# fpga30-serdes-power.net
KiCad netlist of a schematic drawn in Altium Designer
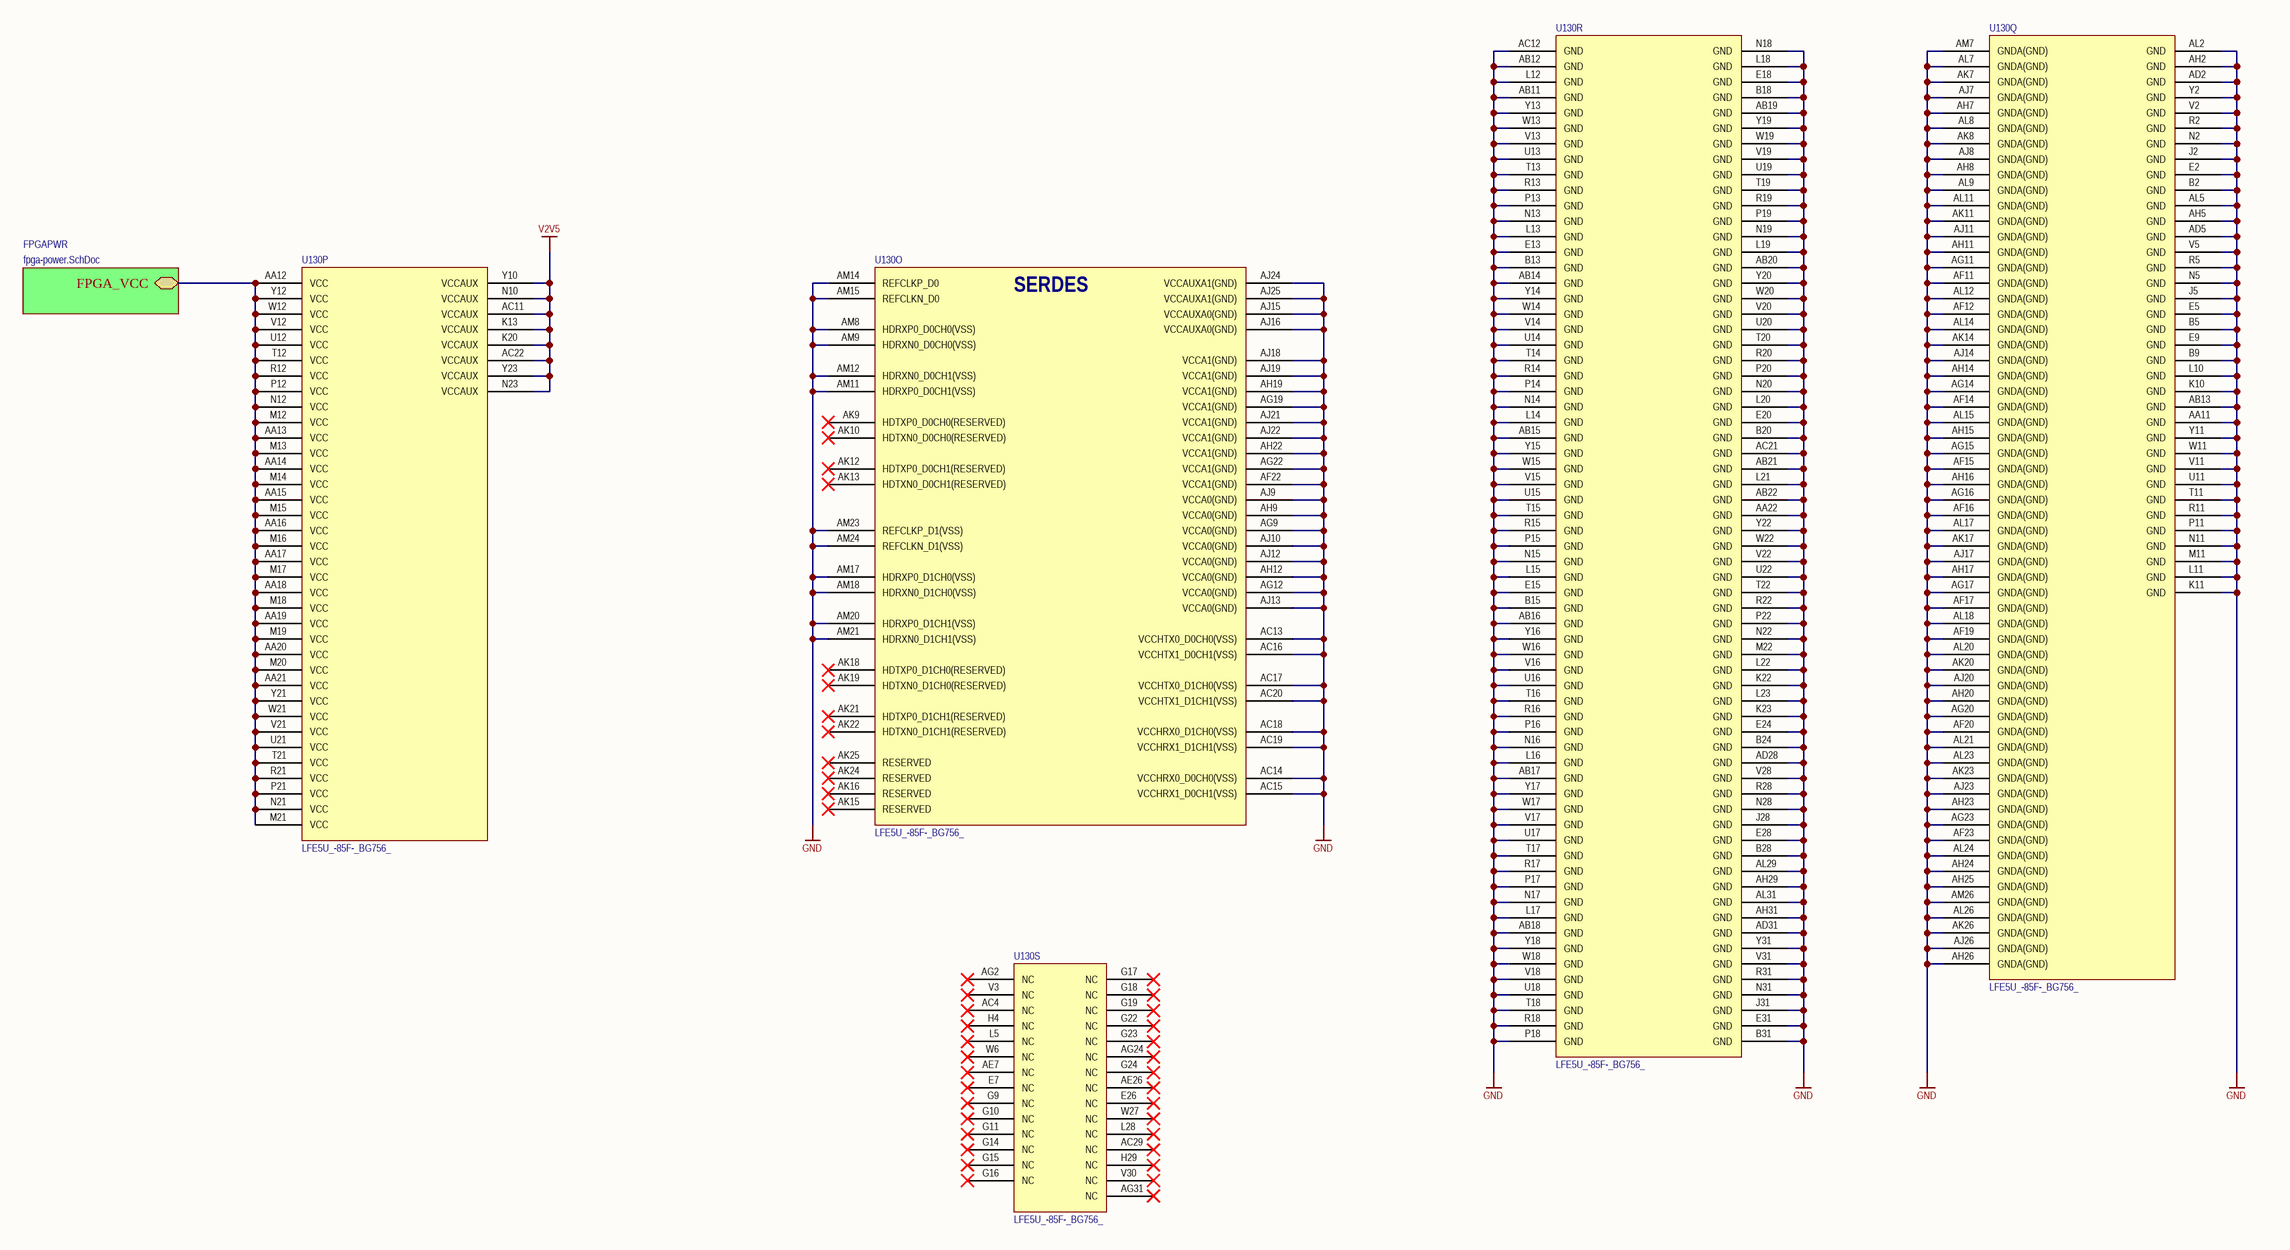
[diagram p0: fpga30-serdes-power.SchDoc]

(export (version "E")
  (design (tool "Eeschema 10.0.6"))
  (components
    (comp (ref "U130")
      (value "LFE5U_-85F-_BG756_")
      (footprint "lattice:caBGA756")
      (description "ECP5 FPGA, 85k LUT, 756-caBGA")
      (fields (field (name "MANUFACTURER") "Lattice Semiconductor"))
      (libsource (lib "lattice") (part "LFE5U_-85F-_BG756_"))
    )
  )
  (nets
    (net (code "1") (name "/FPGA_VCC") (class "Default")
      (node (ref "U130") (pin "AA12") (pinfunction "VCC_AA12") (pintype "power_in"))
      (node (ref "U130") (pin "AA13") (pinfunction "VCC_AA13") (pintype "power_in"))
      (node (ref "U130") (pin "AA14") (pinfunction "VCC_AA14") (pintype "power_in"))
      (node (ref "U130") (pin "AA15") (pinfunction "VCC_AA15") (pintype "power_in"))
      (node (ref "U130") (pin "AA16") (pinfunction "VCC_AA16") (pintype "power_in"))
      (node (ref "U130") (pin "AA17") (pinfunction "VCC_AA17") (pintype "power_in"))
      (node (ref "U130") (pin "AA18") (pinfunction "VCC_AA18") (pintype "power_in"))
      (node (ref "U130") (pin "AA19") (pinfunction "VCC_AA19") (pintype "power_in"))
      (node (ref "U130") (pin "AA20") (pinfunction "VCC_AA20") (pintype "power_in"))
      (node (ref "U130") (pin "AA21") (pinfunction "VCC_AA21") (pintype "power_in"))
      (node (ref "U130") (pin "M12") (pinfunction "VCC_M12") (pintype "power_in"))
      (node (ref "U130") (pin "M13") (pinfunction "VCC_M13") (pintype "power_in"))
      (node (ref "U130") (pin "M14") (pinfunction "VCC_M14") (pintype "power_in"))
      (node (ref "U130") (pin "M15") (pinfunction "VCC_M15") (pintype "power_in"))
      (node (ref "U130") (pin "M16") (pinfunction "VCC_M16") (pintype "power_in"))
      (node (ref "U130") (pin "M17") (pinfunction "VCC_M17") (pintype "power_in"))
      (node (ref "U130") (pin "M18") (pinfunction "VCC_M18") (pintype "power_in"))
      (node (ref "U130") (pin "M19") (pinfunction "VCC_M19") (pintype "power_in"))
      (node (ref "U130") (pin "M20") (pinfunction "VCC_M20") (pintype "power_in"))
      (node (ref "U130") (pin "M21") (pinfunction "VCC_M21") (pintype "power_in"))
      (node (ref "U130") (pin "N12") (pinfunction "VCC_N12") (pintype "power_in"))
      (node (ref "U130") (pin "N21") (pinfunction "VCC_N21") (pintype "power_in"))
      (node (ref "U130") (pin "P12") (pinfunction "VCC_P12") (pintype "power_in"))
      (node (ref "U130") (pin "P21") (pinfunction "VCC_P21") (pintype "power_in"))
      (node (ref "U130") (pin "R12") (pinfunction "VCC_R12") (pintype "power_in"))
      (node (ref "U130") (pin "R21") (pinfunction "VCC_R21") (pintype "power_in"))
      (node (ref "U130") (pin "T12") (pinfunction "VCC_T12") (pintype "power_in"))
      (node (ref "U130") (pin "T21") (pinfunction "VCC_T21") (pintype "power_in"))
      (node (ref "U130") (pin "U12") (pinfunction "VCC_U12") (pintype "power_in"))
      (node (ref "U130") (pin "U21") (pinfunction "VCC_U21") (pintype "power_in"))
      (node (ref "U130") (pin "V12") (pinfunction "VCC_V12") (pintype "power_in"))
      (node (ref "U130") (pin "V21") (pinfunction "VCC_V21") (pintype "power_in"))
      (node (ref "U130") (pin "W12") (pinfunction "VCC_W12") (pintype "power_in"))
      (node (ref "U130") (pin "W21") (pinfunction "VCC_W21") (pintype "power_in"))
      (node (ref "U130") (pin "Y12") (pinfunction "VCC_Y12") (pintype "power_in"))
      (node (ref "U130") (pin "Y21") (pinfunction "VCC_Y21") (pintype "power_in"))
    )
    (net (code "2") (name "GND") (class "Default")
      (node (ref "U130") (pin "AA11") (pinfunction "GND_AA11") (pintype "power_in"))
      (node (ref "U130") (pin "AA22") (pinfunction "GND_AA22") (pintype "power_in"))
      (node (ref "U130") (pin "AB11") (pinfunction "GND_AB11") (pintype "power_in"))
      (node (ref "U130") (pin "AB12") (pinfunction "GND_AB12") (pintype "power_in"))
      (node (ref "U130") (pin "AB13") (pinfunction "GND_AB13") (pintype "power_in"))
      (node (ref "U130") (pin "AB14") (pinfunction "GND_AB14") (pintype "power_in"))
      (node (ref "U130") (pin "AB15") (pinfunction "GND_AB15") (pintype "power_in"))
      (node (ref "U130") (pin "AB16") (pinfunction "GND_AB16") (pintype "power_in"))
      (node (ref "U130") (pin "AB17") (pinfunction "GND_AB17") (pintype "power_in"))
      (node (ref "U130") (pin "AB18") (pinfunction "GND_AB18") (pintype "power_in"))
      (node (ref "U130") (pin "AB19") (pinfunction "GND_AB19") (pintype "power_in"))
      (node (ref "U130") (pin "AB20") (pinfunction "GND_AB20") (pintype "power_in"))
      (node (ref "U130") (pin "AB21") (pinfunction "GND_AB21") (pintype "power_in"))
      (node (ref "U130") (pin "AB22") (pinfunction "GND_AB22") (pintype "power_in"))
      (node (ref "U130") (pin "AC12") (pinfunction "GND_AC12") (pintype "power_in"))
      (node (ref "U130") (pin "AC13") (pinfunction "VCCHTX0_D0CH0(VSS)_AC13") (pintype "power_in"))
      (node (ref "U130") (pin "AC14") (pinfunction "VCCHRX0_D0CH0(VSS)_AC14") (pintype "power_in"))
      (node (ref "U130") (pin "AC15") (pinfunction "VCCHRX1_D0CH1(VSS)_AC15") (pintype "power_in"))
      (node (ref "U130") (pin "AC16") (pinfunction "VCCHTX1_D0CH1(VSS)_AC16") (pintype "power_in"))
      (node (ref "U130") (pin "AC17") (pinfunction "VCCHTX0_D1CH0(VSS)_AC17") (pintype "power_in"))
      (node (ref "U130") (pin "AC18") (pinfunction "VCCHRX0_D1CH0(VSS)_AC18") (pintype "power_in"))
      (node (ref "U130") (pin "AC19") (pinfunction "VCCHRX1_D1CH1(VSS)_AC19") (pintype "power_in"))
      (node (ref "U130") (pin "AC20") (pinfunction "VCCHTX1_D1CH1(VSS)_AC20") (pintype "power_in"))
      (node (ref "U130") (pin "AC21") (pinfunction "GND_AC21") (pintype "power_in"))
      (node (ref "U130") (pin "AD2") (pinfunction "GND_AD2") (pintype "power_in"))
      (node (ref "U130") (pin "AD28") (pinfunction "GND_AD28") (pintype "power_in"))
      (node (ref "U130") (pin "AD31") (pinfunction "GND_AD31") (pintype "power_in"))
      (node (ref "U130") (pin "AD5") (pinfunction "GND_AD5") (pintype "power_in"))
      (node (ref "U130") (pin "AF11") (pinfunction "GNDA(GND)_AF11") (pintype "power_in"))
      (node (ref "U130") (pin "AF12") (pinfunction "GNDA(GND)_AF12") (pintype "power_in"))
      (node (ref "U130") (pin "AF14") (pinfunction "GNDA(GND)_AF14") (pintype "power_in"))
      (node (ref "U130") (pin "AF15") (pinfunction "GNDA(GND)_AF15") (pintype "power_in"))
      (node (ref "U130") (pin "AF16") (pinfunction "GNDA(GND)_AF16") (pintype "power_in"))
      (node (ref "U130") (pin "AF17") (pinfunction "GNDA(GND)_AF17") (pintype "power_in"))
      (node (ref "U130") (pin "AF19") (pinfunction "GNDA(GND)_AF19") (pintype "power_in"))
      (node (ref "U130") (pin "AF20") (pinfunction "GNDA(GND)_AF20") (pintype "power_in"))
      (node (ref "U130") (pin "AF22") (pinfunction "VCCA1(GND)_AF22") (pintype "power_in"))
      (node (ref "U130") (pin "AF23") (pinfunction "GNDA(GND)_AF23") (pintype "power_in"))
      (node (ref "U130") (pin "AG11") (pinfunction "GNDA(GND)_AG11") (pintype "power_in"))
      (node (ref "U130") (pin "AG12") (pinfunction "VCCA0(GND)_AG12") (pintype "power_in"))
      (node (ref "U130") (pin "AG14") (pinfunction "GNDA(GND)_AG14") (pintype "power_in"))
      (node (ref "U130") (pin "AG15") (pinfunction "GNDA(GND)_AG15") (pintype "power_in"))
      (node (ref "U130") (pin "AG16") (pinfunction "GNDA(GND)_AG16") (pintype "power_in"))
      (node (ref "U130") (pin "AG17") (pinfunction "GNDA(GND)_AG17") (pintype "power_in"))
      (node (ref "U130") (pin "AG19") (pinfunction "VCCA1(GND)_AG19") (pintype "power_in"))
      (node (ref "U130") (pin "AG20") (pinfunction "GNDA(GND)_AG20") (pintype "power_in"))
      (node (ref "U130") (pin "AG22") (pinfunction "VCCA1(GND)_AG22") (pintype "power_in"))
      (node (ref "U130") (pin "AG23") (pinfunction "GNDA(GND)_AG23") (pintype "power_in"))
      (node (ref "U130") (pin "AG9") (pinfunction "VCCA0(GND)_AG9") (pintype "power_in"))
      (node (ref "U130") (pin "AH11") (pinfunction "GNDA(GND)_AH11") (pintype "power_in"))
      (node (ref "U130") (pin "AH12") (pinfunction "VCCA0(GND)_AH12") (pintype "power_in"))
      (node (ref "U130") (pin "AH14") (pinfunction "GNDA(GND)_AH14") (pintype "power_in"))
      (node (ref "U130") (pin "AH15") (pinfunction "GNDA(GND)_AH15") (pintype "power_in"))
      (node (ref "U130") (pin "AH16") (pinfunction "GNDA(GND)_AH16") (pintype "power_in"))
      (node (ref "U130") (pin "AH17") (pinfunction "GNDA(GND)_AH17") (pintype "power_in"))
      (node (ref "U130") (pin "AH19") (pinfunction "VCCA1(GND)_AH19") (pintype "power_in"))
      (node (ref "U130") (pin "AH2") (pinfunction "GND_AH2") (pintype "power_in"))
      (node (ref "U130") (pin "AH20") (pinfunction "GNDA(GND)_AH20") (pintype "power_in"))
      (node (ref "U130") (pin "AH22") (pinfunction "VCCA1(GND)_AH22") (pintype "power_in"))
      (node (ref "U130") (pin "AH23") (pinfunction "GNDA(GND)_AH23") (pintype "power_in"))
      (node (ref "U130") (pin "AH24") (pinfunction "GNDA(GND)_AH24") (pintype "power_in"))
      (node (ref "U130") (pin "AH25") (pinfunction "GNDA(GND)_AH25") (pintype "power_in"))
      (node (ref "U130") (pin "AH26") (pinfunction "GNDA(GND)_AH26") (pintype "power_in"))
      (node (ref "U130") (pin "AH29") (pinfunction "GND_AH29") (pintype "power_in"))
      (node (ref "U130") (pin "AH31") (pinfunction "GND_AH31") (pintype "power_in"))
      (node (ref "U130") (pin "AH5") (pinfunction "GND_AH5") (pintype "power_in"))
      (node (ref "U130") (pin "AH7") (pinfunction "GNDA(GND)_AH7") (pintype "power_in"))
      (node (ref "U130") (pin "AH8") (pinfunction "GNDA(GND)_AH8") (pintype "power_in"))
      (node (ref "U130") (pin "AH9") (pinfunction "VCCA0(GND)_AH9") (pintype "power_in"))
      (node (ref "U130") (pin "AJ10") (pinfunction "VCCA0(GND)_AJ10") (pintype "power_in"))
      (node (ref "U130") (pin "AJ11") (pinfunction "GNDA(GND)_AJ11") (pintype "power_in"))
      (node (ref "U130") (pin "AJ12") (pinfunction "VCCA0(GND)_AJ12") (pintype "power_in"))
      (node (ref "U130") (pin "AJ13") (pinfunction "VCCA0(GND)_AJ13") (pintype "power_in"))
      (node (ref "U130") (pin "AJ14") (pinfunction "GNDA(GND)_AJ14") (pintype "power_in"))
      (node (ref "U130") (pin "AJ15") (pinfunction "VCCAUXA0(GND)_AJ15") (pintype "power_in"))
      (node (ref "U130") (pin "AJ16") (pinfunction "VCCAUXA0(GND)_AJ16") (pintype "power_in"))
      (node (ref "U130") (pin "AJ17") (pinfunction "GNDA(GND)_AJ17") (pintype "power_in"))
      (node (ref "U130") (pin "AJ18") (pinfunction "VCCA1(GND)_AJ18") (pintype "power_in"))
      (node (ref "U130") (pin "AJ19") (pinfunction "VCCA1(GND)_AJ19") (pintype "power_in"))
      (node (ref "U130") (pin "AJ20") (pinfunction "GNDA(GND)_AJ20") (pintype "power_in"))
      (node (ref "U130") (pin "AJ21") (pinfunction "VCCA1(GND)_AJ21") (pintype "power_in"))
      (node (ref "U130") (pin "AJ22") (pinfunction "VCCA1(GND)_AJ22") (pintype "power_in"))
      (node (ref "U130") (pin "AJ23") (pinfunction "GNDA(GND)_AJ23") (pintype "power_in"))
      (node (ref "U130") (pin "AJ24") (pinfunction "VCCAUXA1(GND)_AJ24") (pintype "power_in"))
      (node (ref "U130") (pin "AJ25") (pinfunction "VCCAUXA1(GND)_AJ25") (pintype "power_in"))
      (node (ref "U130") (pin "AJ26") (pinfunction "GNDA(GND)_AJ26") (pintype "power_in"))
      (node (ref "U130") (pin "AJ7") (pinfunction "GNDA(GND)_AJ7") (pintype "power_in"))
      (node (ref "U130") (pin "AJ8") (pinfunction "GNDA(GND)_AJ8") (pintype "power_in"))
      (node (ref "U130") (pin "AJ9") (pinfunction "VCCA0(GND)_AJ9") (pintype "power_in"))
      (node (ref "U130") (pin "AK11") (pinfunction "GNDA(GND)_AK11") (pintype "power_in"))
      (node (ref "U130") (pin "AK14") (pinfunction "GNDA(GND)_AK14") (pintype "power_in"))
      (node (ref "U130") (pin "AK17") (pinfunction "GNDA(GND)_AK17") (pintype "power_in"))
      (node (ref "U130") (pin "AK20") (pinfunction "GNDA(GND)_AK20") (pintype "power_in"))
      (node (ref "U130") (pin "AK23") (pinfunction "GNDA(GND)_AK23") (pintype "power_in"))
      (node (ref "U130") (pin "AK26") (pinfunction "GNDA(GND)_AK26") (pintype "power_in"))
      (node (ref "U130") (pin "AK7") (pinfunction "GNDA(GND)_AK7") (pintype "power_in"))
      (node (ref "U130") (pin "AK8") (pinfunction "GNDA(GND)_AK8") (pintype "power_in"))
      (node (ref "U130") (pin "AL11") (pinfunction "GNDA(GND)_AL11") (pintype "power_in"))
      (node (ref "U130") (pin "AL12") (pinfunction "GNDA(GND)_AL12") (pintype "power_in"))
      (node (ref "U130") (pin "AL14") (pinfunction "GNDA(GND)_AL14") (pintype "power_in"))
      (node (ref "U130") (pin "AL15") (pinfunction "GNDA(GND)_AL15") (pintype "power_in"))
      (node (ref "U130") (pin "AL17") (pinfunction "GNDA(GND)_AL17") (pintype "power_in"))
      (node (ref "U130") (pin "AL18") (pinfunction "GNDA(GND)_AL18") (pintype "power_in"))
      (node (ref "U130") (pin "AL2") (pinfunction "GND_AL2") (pintype "power_in"))
      (node (ref "U130") (pin "AL20") (pinfunction "GNDA(GND)_AL20") (pintype "power_in"))
      (node (ref "U130") (pin "AL21") (pinfunction "GNDA(GND)_AL21") (pintype "power_in"))
      (node (ref "U130") (pin "AL23") (pinfunction "GNDA(GND)_AL23") (pintype "power_in"))
      (node (ref "U130") (pin "AL24") (pinfunction "GNDA(GND)_AL24") (pintype "power_in"))
      (node (ref "U130") (pin "AL26") (pinfunction "GNDA(GND)_AL26") (pintype "power_in"))
      (node (ref "U130") (pin "AL29") (pinfunction "GND_AL29") (pintype "power_in"))
      (node (ref "U130") (pin "AL31") (pinfunction "GND_AL31") (pintype "power_in"))
      (node (ref "U130") (pin "AL5") (pinfunction "GND_AL5") (pintype "power_in"))
      (node (ref "U130") (pin "AL7") (pinfunction "GNDA(GND)_AL7") (pintype "power_in"))
      (node (ref "U130") (pin "AL8") (pinfunction "GNDA(GND)_AL8") (pintype "power_in"))
      (node (ref "U130") (pin "AL9") (pinfunction "GNDA(GND)_AL9") (pintype "power_in"))
      (node (ref "U130") (pin "AM11") (pinfunction "HDRXP0_D0CH1(VSS)_AM11") (pintype "passive"))
      (node (ref "U130") (pin "AM12") (pinfunction "HDRXN0_D0CH1(VSS)_AM12") (pintype "passive"))
      (node (ref "U130") (pin "AM14") (pinfunction "REFCLKP_D0_AM14") (pintype "passive"))
      (node (ref "U130") (pin "AM15") (pinfunction "REFCLKN_D0_AM15") (pintype "passive"))
      (node (ref "U130") (pin "AM17") (pinfunction "HDRXP0_D1CH0(VSS)_AM17") (pintype "passive"))
      (node (ref "U130") (pin "AM18") (pinfunction "HDRXN0_D1CH0(VSS)_AM18") (pintype "passive"))
      (node (ref "U130") (pin "AM20") (pinfunction "HDRXP0_D1CH1(VSS)_AM20") (pintype "passive"))
      (node (ref "U130") (pin "AM21") (pinfunction "HDRXN0_D1CH1(VSS)_AM21") (pintype "passive"))
      (node (ref "U130") (pin "AM23") (pinfunction "REFCLKP_D1(VSS)_AM23") (pintype "passive"))
      (node (ref "U130") (pin "AM24") (pinfunction "REFCLKN_D1(VSS)_AM24") (pintype "passive"))
      (node (ref "U130") (pin "AM26") (pinfunction "GNDA(GND)_AM26") (pintype "power_in"))
      (node (ref "U130") (pin "AM7") (pinfunction "GNDA(GND)_AM7") (pintype "power_in"))
      (node (ref "U130") (pin "AM8") (pinfunction "HDRXP0_D0CH0(VSS)_AM8") (pintype "passive"))
      (node (ref "U130") (pin "AM9") (pinfunction "HDRXN0_D0CH0(VSS)_AM9") (pintype "passive"))
      (node (ref "U130") (pin "B13") (pinfunction "GND_B13") (pintype "power_in"))
      (node (ref "U130") (pin "B15") (pinfunction "GND_B15") (pintype "power_in"))
      (node (ref "U130") (pin "B18") (pinfunction "GND_B18") (pintype "power_in"))
      (node (ref "U130") (pin "B2") (pinfunction "GND_B2") (pintype "power_in"))
      (node (ref "U130") (pin "B20") (pinfunction "GND_B20") (pintype "power_in"))
      (node (ref "U130") (pin "B24") (pinfunction "GND_B24") (pintype "power_in"))
      (node (ref "U130") (pin "B28") (pinfunction "GND_B28") (pintype "power_in"))
      (node (ref "U130") (pin "B31") (pinfunction "GND_B31") (pintype "power_in"))
      (node (ref "U130") (pin "B5") (pinfunction "GND_B5") (pintype "power_in"))
      (node (ref "U130") (pin "B9") (pinfunction "GND_B9") (pintype "power_in"))
      (node (ref "U130") (pin "E13") (pinfunction "GND_E13") (pintype "power_in"))
      (node (ref "U130") (pin "E15") (pinfunction "GND_E15") (pintype "power_in"))
      (node (ref "U130") (pin "E18") (pinfunction "GND_E18") (pintype "power_in"))
      (node (ref "U130") (pin "E2") (pinfunction "GND_E2") (pintype "power_in"))
      (node (ref "U130") (pin "E20") (pinfunction "GND_E20") (pintype "power_in"))
      (node (ref "U130") (pin "E24") (pinfunction "GND_E24") (pintype "power_in"))
      (node (ref "U130") (pin "E28") (pinfunction "GND_E28") (pintype "power_in"))
      (node (ref "U130") (pin "E31") (pinfunction "GND_E31") (pintype "power_in"))
      (node (ref "U130") (pin "E5") (pinfunction "GND_E5") (pintype "power_in"))
      (node (ref "U130") (pin "E9") (pinfunction "GND_E9") (pintype "power_in"))
      (node (ref "U130") (pin "J2") (pinfunction "GND_J2") (pintype "power_in"))
      (node (ref "U130") (pin "J28") (pinfunction "GND_J28") (pintype "power_in"))
      (node (ref "U130") (pin "J31") (pinfunction "GND_J31") (pintype "power_in"))
      (node (ref "U130") (pin "J5") (pinfunction "GND_J5") (pintype "power_in"))
      (node (ref "U130") (pin "K10") (pinfunction "GND_K10") (pintype "power_in"))
      (node (ref "U130") (pin "K11") (pinfunction "GND_K11") (pintype "power_in"))
      (node (ref "U130") (pin "K22") (pinfunction "GND_K22") (pintype "power_in"))
      (node (ref "U130") (pin "K23") (pinfunction "GND_K23") (pintype "power_in"))
      (node (ref "U130") (pin "L10") (pinfunction "GND_L10") (pintype "power_in"))
      (node (ref "U130") (pin "L11") (pinfunction "GND_L11") (pintype "power_in"))
      (node (ref "U130") (pin "L12") (pinfunction "GND_L12") (pintype "power_in"))
      (node (ref "U130") (pin "L13") (pinfunction "GND_L13") (pintype "power_in"))
      (node (ref "U130") (pin "L14") (pinfunction "GND_L14") (pintype "power_in"))
      (node (ref "U130") (pin "L15") (pinfunction "GND_L15") (pintype "power_in"))
      (node (ref "U130") (pin "L16") (pinfunction "GND_L16") (pintype "power_in"))
      (node (ref "U130") (pin "L17") (pinfunction "GND_L17") (pintype "power_in"))
      (node (ref "U130") (pin "L18") (pinfunction "GND_L18") (pintype "power_in"))
      (node (ref "U130") (pin "L19") (pinfunction "GND_L19") (pintype "power_in"))
      (node (ref "U130") (pin "L20") (pinfunction "GND_L20") (pintype "power_in"))
      (node (ref "U130") (pin "L21") (pinfunction "GND_L21") (pintype "power_in"))
      (node (ref "U130") (pin "L22") (pinfunction "GND_L22") (pintype "power_in"))
      (node (ref "U130") (pin "L23") (pinfunction "GND_L23") (pintype "power_in"))
      (node (ref "U130") (pin "M11") (pinfunction "GND_M11") (pintype "power_in"))
      (node (ref "U130") (pin "M22") (pinfunction "GND_M22") (pintype "power_in"))
      (node (ref "U130") (pin "N11") (pinfunction "GND_N11") (pintype "power_in"))
      (node (ref "U130") (pin "N13") (pinfunction "GND_N13") (pintype "power_in"))
      (node (ref "U130") (pin "N14") (pinfunction "GND_N14") (pintype "power_in"))
      (node (ref "U130") (pin "N15") (pinfunction "GND_N15") (pintype "power_in"))
      (node (ref "U130") (pin "N16") (pinfunction "GND_N16") (pintype "power_in"))
      (node (ref "U130") (pin "N17") (pinfunction "GND_N17") (pintype "power_in"))
      (node (ref "U130") (pin "N18") (pinfunction "GND_N18") (pintype "power_in"))
      (node (ref "U130") (pin "N19") (pinfunction "GND_N19") (pintype "power_in"))
      (node (ref "U130") (pin "N2") (pinfunction "GND_N2") (pintype "power_in"))
      (node (ref "U130") (pin "N20") (pinfunction "GND_N20") (pintype "power_in"))
      (node (ref "U130") (pin "N22") (pinfunction "GND_N22") (pintype "power_in"))
      (node (ref "U130") (pin "N28") (pinfunction "GND_N28") (pintype "power_in"))
      (node (ref "U130") (pin "N31") (pinfunction "GND_N31") (pintype "power_in"))
      (node (ref "U130") (pin "N5") (pinfunction "GND_N5") (pintype "power_in"))
      (node (ref "U130") (pin "P11") (pinfunction "GND_P11") (pintype "power_in"))
      (node (ref "U130") (pin "P13") (pinfunction "GND_P13") (pintype "power_in"))
      (node (ref "U130") (pin "P14") (pinfunction "GND_P14") (pintype "power_in"))
      (node (ref "U130") (pin "P15") (pinfunction "GND_P15") (pintype "power_in"))
      (node (ref "U130") (pin "P16") (pinfunction "GND_P16") (pintype "power_in"))
      (node (ref "U130") (pin "P17") (pinfunction "GND_P17") (pintype "power_in"))
      (node (ref "U130") (pin "P18") (pinfunction "GND_P18") (pintype "power_in"))
      (node (ref "U130") (pin "P19") (pinfunction "GND_P19") (pintype "power_in"))
      (node (ref "U130") (pin "P20") (pinfunction "GND_P20") (pintype "power_in"))
      (node (ref "U130") (pin "P22") (pinfunction "GND_P22") (pintype "power_in"))
      (node (ref "U130") (pin "R11") (pinfunction "GND_R11") (pintype "power_in"))
      (node (ref "U130") (pin "R13") (pinfunction "GND_R13") (pintype "power_in"))
      (node (ref "U130") (pin "R14") (pinfunction "GND_R14") (pintype "power_in"))
      (node (ref "U130") (pin "R15") (pinfunction "GND_R15") (pintype "power_in"))
      (node (ref "U130") (pin "R16") (pinfunction "GND_R16") (pintype "power_in"))
      (node (ref "U130") (pin "R17") (pinfunction "GND_R17") (pintype "power_in"))
      (node (ref "U130") (pin "R18") (pinfunction "GND_R18") (pintype "power_in"))
      (node (ref "U130") (pin "R19") (pinfunction "GND_R19") (pintype "power_in"))
      (node (ref "U130") (pin "R2") (pinfunction "GND_R2") (pintype "power_in"))
      (node (ref "U130") (pin "R20") (pinfunction "GND_R20") (pintype "power_in"))
      (node (ref "U130") (pin "R22") (pinfunction "GND_R22") (pintype "power_in"))
      (node (ref "U130") (pin "R28") (pinfunction "GND_R28") (pintype "power_in"))
      (node (ref "U130") (pin "R31") (pinfunction "GND_R31") (pintype "power_in"))
      (node (ref "U130") (pin "R5") (pinfunction "GND_R5") (pintype "power_in"))
      (node (ref "U130") (pin "T11") (pinfunction "GND_T11") (pintype "power_in"))
      (node (ref "U130") (pin "T13") (pinfunction "GND_T13") (pintype "power_in"))
      (node (ref "U130") (pin "T14") (pinfunction "GND_T14") (pintype "power_in"))
      (node (ref "U130") (pin "T15") (pinfunction "GND_T15") (pintype "power_in"))
      (node (ref "U130") (pin "T16") (pinfunction "GND_T16") (pintype "power_in"))
      (node (ref "U130") (pin "T17") (pinfunction "GND_T17") (pintype "power_in"))
      (node (ref "U130") (pin "T18") (pinfunction "GND_T18") (pintype "power_in"))
      (node (ref "U130") (pin "T19") (pinfunction "GND_T19") (pintype "power_in"))
      (node (ref "U130") (pin "T20") (pinfunction "GND_T20") (pintype "power_in"))
      (node (ref "U130") (pin "T22") (pinfunction "GND_T22") (pintype "power_in"))
      (node (ref "U130") (pin "U11") (pinfunction "GND_U11") (pintype "power_in"))
      (node (ref "U130") (pin "U13") (pinfunction "GND_U13") (pintype "power_in"))
      (node (ref "U130") (pin "U14") (pinfunction "GND_U14") (pintype "power_in"))
      (node (ref "U130") (pin "U15") (pinfunction "GND_U15") (pintype "power_in"))
      (node (ref "U130") (pin "U16") (pinfunction "GND_U16") (pintype "power_in"))
      (node (ref "U130") (pin "U17") (pinfunction "GND_U17") (pintype "power_in"))
      (node (ref "U130") (pin "U18") (pinfunction "GND_U18") (pintype "power_in"))
      (node (ref "U130") (pin "U19") (pinfunction "GND_U19") (pintype "power_in"))
      (node (ref "U130") (pin "U20") (pinfunction "GND_U20") (pintype "power_in"))
      (node (ref "U130") (pin "U22") (pinfunction "GND_U22") (pintype "power_in"))
      (node (ref "U130") (pin "V11") (pinfunction "GND_V11") (pintype "power_in"))
      (node (ref "U130") (pin "V13") (pinfunction "GND_V13") (pintype "power_in"))
      (node (ref "U130") (pin "V14") (pinfunction "GND_V14") (pintype "power_in"))
      (node (ref "U130") (pin "V15") (pinfunction "GND_V15") (pintype "power_in"))
      (node (ref "U130") (pin "V16") (pinfunction "GND_V16") (pintype "power_in"))
      (node (ref "U130") (pin "V17") (pinfunction "GND_V17") (pintype "power_in"))
      (node (ref "U130") (pin "V18") (pinfunction "GND_V18") (pintype "power_in"))
      (node (ref "U130") (pin "V19") (pinfunction "GND_V19") (pintype "power_in"))
      (node (ref "U130") (pin "V2") (pinfunction "GND_V2") (pintype "power_in"))
      (node (ref "U130") (pin "V20") (pinfunction "GND_V20") (pintype "power_in"))
      (node (ref "U130") (pin "V22") (pinfunction "GND_V22") (pintype "power_in"))
      (node (ref "U130") (pin "V28") (pinfunction "GND_V28") (pintype "power_in"))
      (node (ref "U130") (pin "V31") (pinfunction "GND_V31") (pintype "power_in"))
      (node (ref "U130") (pin "V5") (pinfunction "GND_V5") (pintype "power_in"))
      (node (ref "U130") (pin "W11") (pinfunction "GND_W11") (pintype "power_in"))
      (node (ref "U130") (pin "W13") (pinfunction "GND_W13") (pintype "power_in"))
      (node (ref "U130") (pin "W14") (pinfunction "GND_W14") (pintype "power_in"))
      (node (ref "U130") (pin "W15") (pinfunction "GND_W15") (pintype "power_in"))
      (node (ref "U130") (pin "W16") (pinfunction "GND_W16") (pintype "power_in"))
      (node (ref "U130") (pin "W17") (pinfunction "GND_W17") (pintype "power_in"))
      (node (ref "U130") (pin "W18") (pinfunction "GND_W18") (pintype "power_in"))
      (node (ref "U130") (pin "W19") (pinfunction "GND_W19") (pintype "power_in"))
      (node (ref "U130") (pin "W20") (pinfunction "GND_W20") (pintype "power_in"))
      (node (ref "U130") (pin "W22") (pinfunction "GND_W22") (pintype "power_in"))
      (node (ref "U130") (pin "Y11") (pinfunction "GND_Y11") (pintype "power_in"))
      (node (ref "U130") (pin "Y13") (pinfunction "GND_Y13") (pintype "power_in"))
      (node (ref "U130") (pin "Y14") (pinfunction "GND_Y14") (pintype "power_in"))
      (node (ref "U130") (pin "Y15") (pinfunction "GND_Y15") (pintype "power_in"))
      (node (ref "U130") (pin "Y16") (pinfunction "GND_Y16") (pintype "power_in"))
      (node (ref "U130") (pin "Y17") (pinfunction "GND_Y17") (pintype "power_in"))
      (node (ref "U130") (pin "Y18") (pinfunction "GND_Y18") (pintype "power_in"))
      (node (ref "U130") (pin "Y19") (pinfunction "GND_Y19") (pintype "power_in"))
      (node (ref "U130") (pin "Y2") (pinfunction "GND_Y2") (pintype "power_in"))
      (node (ref "U130") (pin "Y20") (pinfunction "GND_Y20") (pintype "power_in"))
      (node (ref "U130") (pin "Y22") (pinfunction "GND_Y22") (pintype "power_in"))
      (node (ref "U130") (pin "Y31") (pinfunction "GND_Y31") (pintype "power_in"))
    )
    (net (code "3") (name "V2V5") (class "Default")
      (node (ref "U130") (pin "AC11") (pinfunction "VCCAUX_AC11") (pintype "power_in"))
      (node (ref "U130") (pin "AC22") (pinfunction "VCCAUX_AC22") (pintype "power_in"))
      (node (ref "U130") (pin "K13") (pinfunction "VCCAUX_K13") (pintype "power_in"))
      (node (ref "U130") (pin "K20") (pinfunction "VCCAUX_K20") (pintype "power_in"))
      (node (ref "U130") (pin "N10") (pinfunction "VCCAUX_N10") (pintype "power_in"))
      (node (ref "U130") (pin "N23") (pinfunction "VCCAUX_N23") (pintype "power_in"))
      (node (ref "U130") (pin "Y10") (pinfunction "VCCAUX_Y10") (pintype "power_in"))
      (node (ref "U130") (pin "Y23") (pinfunction "VCCAUX_Y23") (pintype "power_in"))
    )
    (net (code "4") (name "unconnected-(U130O-HDTXN0_D0CH0(RESERVED)-PadAK10)") (class "Default")
      (node (ref "U130") (pin "AK10") (pinfunction "HDTXN0_D0CH0(RESERVED)_AK10") (pintype "passive+no_connect"))
    )
    (net (code "5") (name "unconnected-(U130O-HDTXN0_D0CH1(RESERVED)-PadAK13)") (class "Default")
      (node (ref "U130") (pin "AK13") (pinfunction "HDTXN0_D0CH1(RESERVED)_AK13") (pintype "passive+no_connect"))
    )
    (net (code "6") (name "unconnected-(U130O-HDTXN0_D1CH0(RESERVED)-PadAK19)") (class "Default")
      (node (ref "U130") (pin "AK19") (pinfunction "HDTXN0_D1CH0(RESERVED)_AK19") (pintype "passive+no_connect"))
    )
    (net (code "7") (name "unconnected-(U130O-HDTXN0_D1CH1(RESERVED)-PadAK22)") (class "Default")
      (node (ref "U130") (pin "AK22") (pinfunction "HDTXN0_D1CH1(RESERVED)_AK22") (pintype "passive+no_connect"))
    )
    (net (code "8") (name "unconnected-(U130O-HDTXP0_D0CH0(RESERVED)-PadAK9)") (class "Default")
      (node (ref "U130") (pin "AK9") (pinfunction "HDTXP0_D0CH0(RESERVED)_AK9") (pintype "passive+no_connect"))
    )
    (net (code "9") (name "unconnected-(U130O-HDTXP0_D0CH1(RESERVED)-PadAK12)") (class "Default")
      (node (ref "U130") (pin "AK12") (pinfunction "HDTXP0_D0CH1(RESERVED)_AK12") (pintype "passive+no_connect"))
    )
    (net (code "10") (name "unconnected-(U130O-HDTXP0_D1CH0(RESERVED)-PadAK18)") (class "Default")
      (node (ref "U130") (pin "AK18") (pinfunction "HDTXP0_D1CH0(RESERVED)_AK18") (pintype "passive+no_connect"))
    )
    (net (code "11") (name "unconnected-(U130O-HDTXP0_D1CH1(RESERVED)-PadAK21)") (class "Default")
      (node (ref "U130") (pin "AK21") (pinfunction "HDTXP0_D1CH1(RESERVED)_AK21") (pintype "passive+no_connect"))
    )
    (net (code "12") (name "unconnected-(U130O-RESERVED-PadAK15)") (class "Default")
      (node (ref "U130") (pin "AK15") (pinfunction "RESERVED_AK15") (pintype "passive+no_connect"))
    )
    (net (code "13") (name "unconnected-(U130O-RESERVED-PadAK16)") (class "Default")
      (node (ref "U130") (pin "AK16") (pinfunction "RESERVED_AK16") (pintype "passive+no_connect"))
    )
    (net (code "14") (name "unconnected-(U130O-RESERVED-PadAK24)") (class "Default")
      (node (ref "U130") (pin "AK24") (pinfunction "RESERVED_AK24") (pintype "passive+no_connect"))
    )
    (net (code "15") (name "unconnected-(U130O-RESERVED-PadAK25)") (class "Default")
      (node (ref "U130") (pin "AK25") (pinfunction "RESERVED_AK25") (pintype "passive+no_connect"))
    )
    (net (code "16") (name "unconnected-(U130S-NC-PadAC4)") (class "Default")
      (node (ref "U130") (pin "AC4") (pinfunction "NC_AC4") (pintype "passive+no_connect"))
    )
    (net (code "17") (name "unconnected-(U130S-NC-PadAC29)") (class "Default")
      (node (ref "U130") (pin "AC29") (pinfunction "NC_AC29") (pintype "passive+no_connect"))
    )
    (net (code "18") (name "unconnected-(U130S-NC-PadAE7)") (class "Default")
      (node (ref "U130") (pin "AE7") (pinfunction "NC_AE7") (pintype "passive+no_connect"))
    )
    (net (code "19") (name "unconnected-(U130S-NC-PadAE26)") (class "Default")
      (node (ref "U130") (pin "AE26") (pinfunction "NC_AE26") (pintype "passive+no_connect"))
    )
    (net (code "20") (name "unconnected-(U130S-NC-PadAG2)") (class "Default")
      (node (ref "U130") (pin "AG2") (pinfunction "NC_AG2") (pintype "passive+no_connect"))
    )
    (net (code "21") (name "unconnected-(U130S-NC-PadAG24)") (class "Default")
      (node (ref "U130") (pin "AG24") (pinfunction "NC_AG24") (pintype "passive+no_connect"))
    )
    (net (code "22") (name "unconnected-(U130S-NC-PadAG31)") (class "Default")
      (node (ref "U130") (pin "AG31") (pinfunction "NC_AG31") (pintype "passive+no_connect"))
    )
    (net (code "23") (name "unconnected-(U130S-NC-PadE7)") (class "Default")
      (node (ref "U130") (pin "E7") (pinfunction "NC_E7") (pintype "passive+no_connect"))
    )
    (net (code "24") (name "unconnected-(U130S-NC-PadE26)") (class "Default")
      (node (ref "U130") (pin "E26") (pinfunction "NC_E26") (pintype "passive+no_connect"))
    )
    (net (code "25") (name "unconnected-(U130S-NC-PadG9)") (class "Default")
      (node (ref "U130") (pin "G9") (pinfunction "NC_G9") (pintype "passive+no_connect"))
    )
    (net (code "26") (name "unconnected-(U130S-NC-PadG10)") (class "Default")
      (node (ref "U130") (pin "G10") (pinfunction "NC_G10") (pintype "passive+no_connect"))
    )
    (net (code "27") (name "unconnected-(U130S-NC-PadG11)") (class "Default")
      (node (ref "U130") (pin "G11") (pinfunction "NC_G11") (pintype "passive+no_connect"))
    )
    (net (code "28") (name "unconnected-(U130S-NC-PadG14)") (class "Default")
      (node (ref "U130") (pin "G14") (pinfunction "NC_G14") (pintype "passive+no_connect"))
    )
    (net (code "29") (name "unconnected-(U130S-NC-PadG15)") (class "Default")
      (node (ref "U130") (pin "G15") (pinfunction "NC_G15") (pintype "passive+no_connect"))
    )
    (net (code "30") (name "unconnected-(U130S-NC-PadG16)") (class "Default")
      (node (ref "U130") (pin "G16") (pinfunction "NC_G16") (pintype "passive+no_connect"))
    )
    (net (code "31") (name "unconnected-(U130S-NC-PadG17)") (class "Default")
      (node (ref "U130") (pin "G17") (pinfunction "NC_G17") (pintype "passive+no_connect"))
    )
    (net (code "32") (name "unconnected-(U130S-NC-PadG18)") (class "Default")
      (node (ref "U130") (pin "G18") (pinfunction "NC_G18") (pintype "passive+no_connect"))
    )
    (net (code "33") (name "unconnected-(U130S-NC-PadG19)") (class "Default")
      (node (ref "U130") (pin "G19") (pinfunction "NC_G19") (pintype "passive+no_connect"))
    )
    (net (code "34") (name "unconnected-(U130S-NC-PadG22)") (class "Default")
      (node (ref "U130") (pin "G22") (pinfunction "NC_G22") (pintype "passive+no_connect"))
    )
    (net (code "35") (name "unconnected-(U130S-NC-PadG23)") (class "Default")
      (node (ref "U130") (pin "G23") (pinfunction "NC_G23") (pintype "passive+no_connect"))
    )
    (net (code "36") (name "unconnected-(U130S-NC-PadG24)") (class "Default")
      (node (ref "U130") (pin "G24") (pinfunction "NC_G24") (pintype "passive+no_connect"))
    )
    (net (code "37") (name "unconnected-(U130S-NC-PadH4)") (class "Default")
      (node (ref "U130") (pin "H4") (pinfunction "NC_H4") (pintype "passive+no_connect"))
    )
    (net (code "38") (name "unconnected-(U130S-NC-PadH29)") (class "Default")
      (node (ref "U130") (pin "H29") (pinfunction "NC_H29") (pintype "passive+no_connect"))
    )
    (net (code "39") (name "unconnected-(U130S-NC-PadL5)") (class "Default")
      (node (ref "U130") (pin "L5") (pinfunction "NC_L5") (pintype "passive+no_connect"))
    )
    (net (code "40") (name "unconnected-(U130S-NC-PadL28)") (class "Default")
      (node (ref "U130") (pin "L28") (pinfunction "NC_L28") (pintype "passive+no_connect"))
    )
    (net (code "41") (name "unconnected-(U130S-NC-PadV3)") (class "Default")
      (node (ref "U130") (pin "V3") (pinfunction "NC_V3") (pintype "passive+no_connect"))
    )
    (net (code "42") (name "unconnected-(U130S-NC-PadV30)") (class "Default")
      (node (ref "U130") (pin "V30") (pinfunction "NC_V30") (pintype "passive+no_connect"))
    )
    (net (code "43") (name "unconnected-(U130S-NC-PadW6)") (class "Default")
      (node (ref "U130") (pin "W6") (pinfunction "NC_W6") (pintype "passive+no_connect"))
    )
    (net (code "44") (name "unconnected-(U130S-NC-PadW27)") (class "Default")
      (node (ref "U130") (pin "W27") (pinfunction "NC_W27") (pintype "passive+no_connect"))
    )
  )
)
